# Hamamatsu_acond.net
KiCad netlist of a schematic drawn in Altium Designer
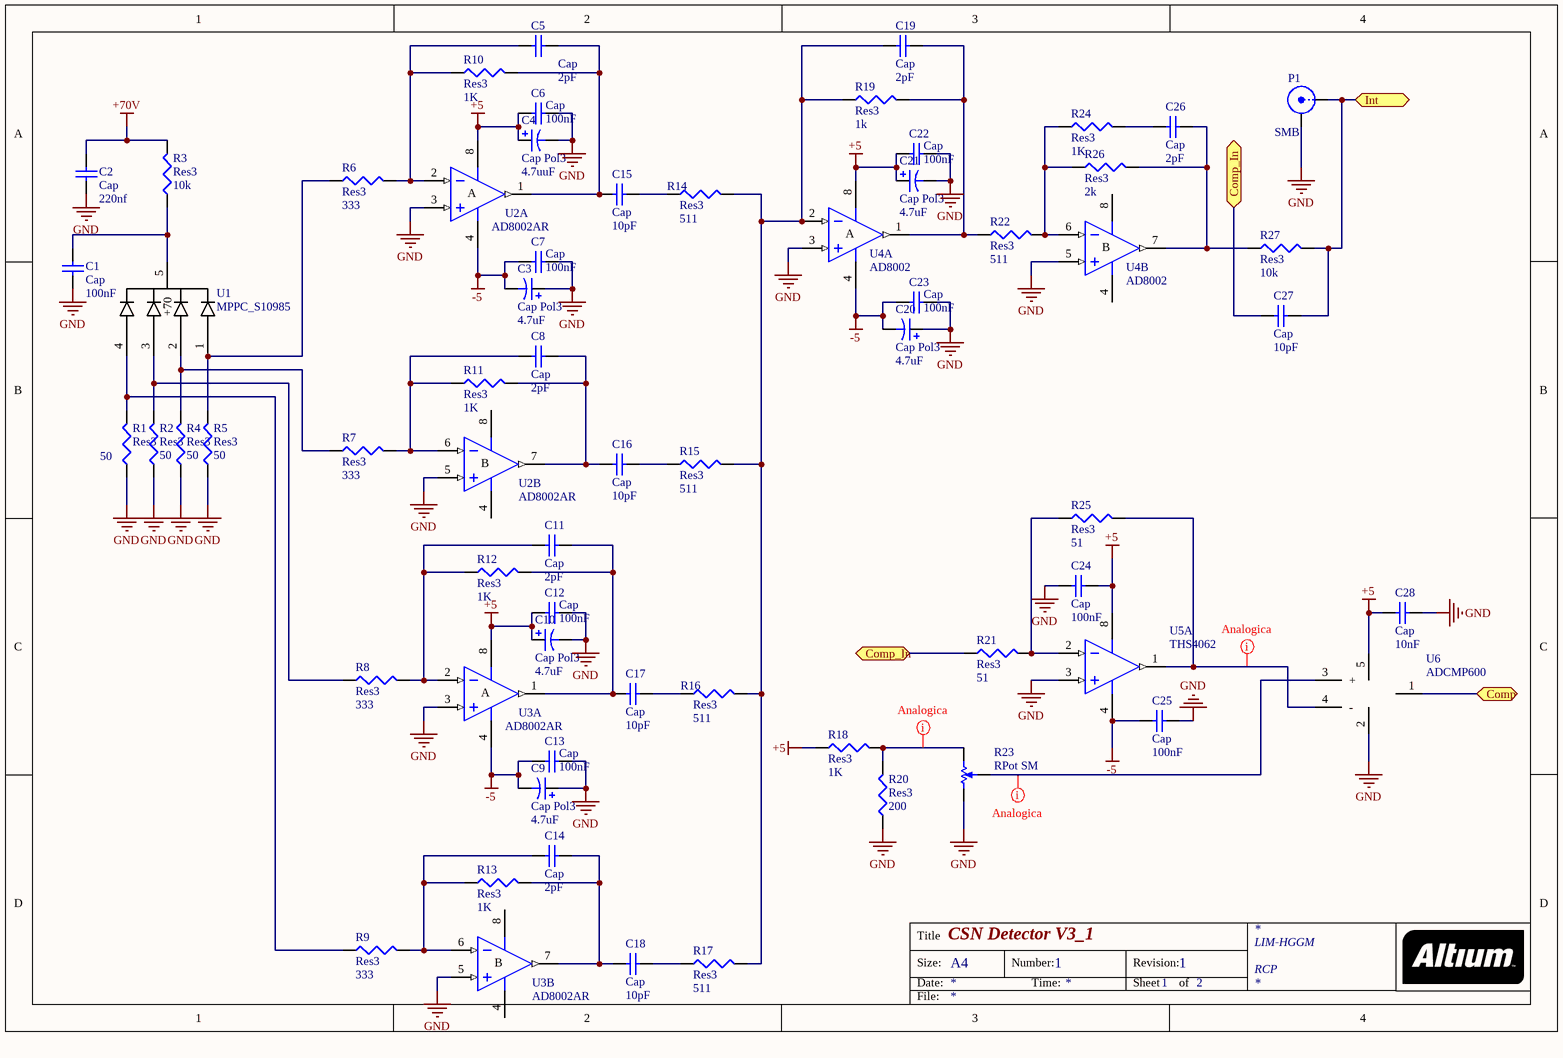
[diagram p0: Hamamatsu_acond.SchDoc]

(export (version "E")
  (design (tool "Eeschema 10.0.6"))
  (components
    (comp (ref "C1")
      (value "Cap")
      (footprint "C0805")
      (description "Capacitor")
      (fields (field (name "ALTIUM_VALUE") "100nF") (field (name "PUBLISHER") "Altium Limited"))
      (libsource (lib "Miscellaneous Devices") (part "Cap"))
    )
    (comp (ref "C2")
      (value "Cap")
      (footprint "C0805")
      (description "Capacitor")
      (fields (field (name "ALTIUM_VALUE") "220nf") (field (name "PUBLISHER") "Altium Limited"))
      (libsource (lib "Miscellaneous Devices") (part "Cap"))
    )
    (comp (ref "C3")
      (value "Cap Pol3")
      (footprint "6-0805_N")
      (description "Polarized Capacitor (Surface Mount)")
      (fields (field (name "ALTIUM_VALUE") "4.7uF") (field (name "PUBLISHER") "Altium Limited"))
      (libsource (lib "Miscellaneous Devices") (part "Cap Pol3"))
    )
    (comp (ref "C4")
      (value "Cap Pol3")
      (footprint "6-0805_N")
      (description "Polarized Capacitor (Surface Mount)")
      (fields (field (name "ALTIUM_VALUE") "4.7uuF") (field (name "PUBLISHER") "Altium Limited"))
      (libsource (lib "Miscellaneous Devices") (part "Cap Pol3"))
    )
    (comp (ref "C5")
      (value "Cap")
      (footprint "C0805")
      (description "Capacitor")
      (fields (field (name "ALTIUM_VALUE") "2pF") (field (name "PUBLISHER") "Altium Limited"))
      (libsource (lib "Miscellaneous Devices") (part "Cap"))
    )
    (comp (ref "C6")
      (value "Cap")
      (footprint "6-0805_N")
      (description "Capacitor")
      (fields (field (name "ALTIUM_VALUE") "100nF") (field (name "PUBLISHER") "Altium Limited"))
      (libsource (lib "Miscellaneous Devices") (part "Cap"))
    )
    (comp (ref "C7")
      (value "Cap")
      (footprint "6-0805_N")
      (description "Capacitor")
      (fields (field (name "ALTIUM_VALUE") "100nF") (field (name "PUBLISHER") "Altium Limited"))
      (libsource (lib "Miscellaneous Devices") (part "Cap"))
    )
    (comp (ref "C8")
      (value "Cap")
      (footprint "C0805")
      (description "Capacitor")
      (fields (field (name "ALTIUM_VALUE") "2pF") (field (name "PUBLISHER") "Altium Limited"))
      (libsource (lib "Miscellaneous Devices") (part "Cap"))
    )
    (comp (ref "C9")
      (value "Cap Pol3")
      (footprint "6-0805_N")
      (description "Polarized Capacitor (Surface Mount)")
      (fields (field (name "ALTIUM_VALUE") "4.7uF") (field (name "PUBLISHER") "Altium Limited"))
      (libsource (lib "Miscellaneous Devices") (part "Cap Pol3"))
    )
    (comp (ref "C10")
      (value "Cap Pol3")
      (footprint "6-0805_N")
      (description "Polarized Capacitor (Surface Mount)")
      (fields (field (name "ALTIUM_VALUE") "4.7uF") (field (name "PUBLISHER") "Altium Limited"))
      (libsource (lib "Miscellaneous Devices") (part "Cap Pol3"))
    )
    (comp (ref "C11")
      (value "Cap")
      (footprint "C0805")
      (description "Capacitor")
      (fields (field (name "ALTIUM_VALUE") "2pF") (field (name "PUBLISHER") "Altium Limited"))
      (libsource (lib "Miscellaneous Devices") (part "Cap"))
    )
    (comp (ref "C12")
      (value "Cap")
      (footprint "6-0805_N")
      (description "Capacitor")
      (fields (field (name "ALTIUM_VALUE") "100nF") (field (name "PUBLISHER") "Altium Limited"))
      (libsource (lib "Miscellaneous Devices") (part "Cap"))
    )
    (comp (ref "C13")
      (value "Cap")
      (footprint "6-0805_N")
      (description "Capacitor")
      (fields (field (name "ALTIUM_VALUE") "100nF") (field (name "PUBLISHER") "Altium Limited"))
      (libsource (lib "Miscellaneous Devices") (part "Cap"))
    )
    (comp (ref "C14")
      (value "Cap")
      (footprint "C0805")
      (description "Capacitor")
      (fields (field (name "ALTIUM_VALUE") "2pF") (field (name "PUBLISHER") "Altium Limited"))
      (libsource (lib "Miscellaneous Devices") (part "Cap"))
    )
    (comp (ref "C15")
      (value "Cap")
      (footprint "C0805")
      (description "Capacitor")
      (fields (field (name "ALTIUM_VALUE") "10pF") (field (name "PUBLISHER") "Altium Limited"))
      (libsource (lib "Miscellaneous Devices") (part "Cap"))
    )
    (comp (ref "C16")
      (value "Cap")
      (footprint "C0805")
      (description "Capacitor")
      (fields (field (name "ALTIUM_VALUE") "10pF") (field (name "PUBLISHER") "Altium Limited"))
      (libsource (lib "Miscellaneous Devices") (part "Cap"))
    )
    (comp (ref "C17")
      (value "Cap")
      (footprint "C0805")
      (description "Capacitor")
      (fields (field (name "ALTIUM_VALUE") "10pF") (field (name "PUBLISHER") "Altium Limited"))
      (libsource (lib "Miscellaneous Devices") (part "Cap"))
    )
    (comp (ref "C18")
      (value "Cap")
      (footprint "C0805")
      (description "Capacitor")
      (fields (field (name "ALTIUM_VALUE") "10pF") (field (name "PUBLISHER") "Altium Limited"))
      (libsource (lib "Miscellaneous Devices") (part "Cap"))
    )
    (comp (ref "C19")
      (value "Cap")
      (footprint "C0805")
      (description "Capacitor")
      (fields (field (name "ALTIUM_VALUE") "2pF") (field (name "PUBLISHER") "Altium Limited"))
      (libsource (lib "Miscellaneous Devices") (part "Cap"))
    )
    (comp (ref "C20")
      (value "Cap Pol3")
      (footprint "6-0805_N")
      (description "Polarized Capacitor (Surface Mount)")
      (fields (field (name "ALTIUM_VALUE") "4.7uF") (field (name "PUBLISHER") "Altium Limited"))
      (libsource (lib "Miscellaneous Devices") (part "Cap Pol3"))
    )
    (comp (ref "C21")
      (value "Cap Pol3")
      (footprint "6-0805_N")
      (description "Polarized Capacitor (Surface Mount)")
      (fields (field (name "ALTIUM_VALUE") "4.7uF") (field (name "PUBLISHER") "Altium Limited"))
      (libsource (lib "Miscellaneous Devices") (part "Cap Pol3"))
    )
    (comp (ref "C22")
      (value "Cap")
      (footprint "6-0805_N")
      (description "Capacitor")
      (fields (field (name "ALTIUM_VALUE") "100nF") (field (name "PUBLISHER") "Altium Limited"))
      (libsource (lib "Miscellaneous Devices") (part "Cap"))
    )
    (comp (ref "C23")
      (value "Cap")
      (footprint "6-0805_N")
      (description "Capacitor")
      (fields (field (name "ALTIUM_VALUE") "100nF") (field (name "PUBLISHER") "Altium Limited"))
      (libsource (lib "Miscellaneous Devices") (part "Cap"))
    )
    (comp (ref "C24")
      (value "Cap")
      (footprint "6-0805_N")
      (description "Capacitor")
      (fields (field (name "ALTIUM_VALUE") "100nF") (field (name "PUBLISHER") "Altium Limited"))
      (libsource (lib "Miscellaneous Devices") (part "Cap"))
    )
    (comp (ref "C25")
      (value "Cap")
      (footprint "6-0805_N")
      (description "Capacitor")
      (fields (field (name "ALTIUM_VALUE") "100nF") (field (name "PUBLISHER") "Altium Limited"))
      (libsource (lib "Miscellaneous Devices") (part "Cap"))
    )
    (comp (ref "C26")
      (value "Cap")
      (footprint "C0805")
      (description "Capacitor")
      (fields (field (name "ALTIUM_VALUE") "2pF") (field (name "PUBLISHER") "Altium Limited"))
      (libsource (lib "Miscellaneous Devices") (part "Cap"))
    )
    (comp (ref "C27")
      (value "Cap")
      (footprint "C0805")
      (description "Capacitor")
      (fields (field (name "ALTIUM_VALUE") "10pF") (field (name "PUBLISHER") "Altium Limited"))
      (libsource (lib "Miscellaneous Devices") (part "Cap"))
    )
    (comp (ref "C28")
      (value "Cap")
      (footprint "6-0805_N")
      (description "Capacitor")
      (fields (field (name "ALTIUM_VALUE") "10nF") (field (name "PUBLISHER") "Altium Limited"))
      (libsource (lib "Miscellaneous Devices") (part "Cap"))
    )
    (comp (ref "P1")
      (value "SMB")
      (footprint "SMB_V-RJ45")
      (description "SMB Straight Connector")
      (fields (field (name "PUBLISHER") "Altium Limited"))
      (libsource (lib "Miscellaneous Connectors") (part "SMB"))
    )
    (comp (ref "R1")
      (value "Res3")
      (footprint "6-0805_N")
      (description "Resistor")
      (fields (field (name "ALTIUM_VALUE") "50") (field (name "PUBLISHER") "Altium Limited"))
      (libsource (lib "Miscellaneous Devices") (part "Res3"))
    )
    (comp (ref "R2")
      (value "Res3")
      (footprint "6-0805_N")
      (description "Resistor")
      (fields (field (name "ALTIUM_VALUE") "50") (field (name "PUBLISHER") "Altium Limited"))
      (libsource (lib "Miscellaneous Devices") (part "Res3"))
    )
    (comp (ref "R3")
      (value "Res3")
      (footprint "6-0805_N")
      (description "Resistor")
      (fields (field (name "ALTIUM_VALUE") "10k") (field (name "PUBLISHER") "Altium Limited"))
      (libsource (lib "Miscellaneous Devices") (part "Res3"))
    )
    (comp (ref "R4")
      (value "Res3")
      (footprint "6-0805_N")
      (description "Resistor")
      (fields (field (name "ALTIUM_VALUE") "50") (field (name "PUBLISHER") "Altium Limited"))
      (libsource (lib "Miscellaneous Devices") (part "Res3"))
    )
    (comp (ref "R5")
      (value "Res3")
      (footprint "6-0805_N")
      (description "Resistor")
      (fields (field (name "ALTIUM_VALUE") "50") (field (name "PUBLISHER") "Altium Limited"))
      (libsource (lib "Miscellaneous Devices") (part "Res3"))
    )
    (comp (ref "R6")
      (value "Res3")
      (footprint "6-0805_N")
      (description "Resistor")
      (fields (field (name "ALTIUM_VALUE") "333") (field (name "PUBLISHER") "Altium Limited"))
      (libsource (lib "Miscellaneous Devices") (part "Res3"))
    )
    (comp (ref "R7")
      (value "Res3")
      (footprint "6-0805_N")
      (description "Resistor")
      (fields (field (name "ALTIUM_VALUE") "333") (field (name "PUBLISHER") "Altium Limited"))
      (libsource (lib "Miscellaneous Devices") (part "Res3"))
    )
    (comp (ref "R8")
      (value "Res3")
      (footprint "6-0805_N")
      (description "Resistor")
      (fields (field (name "ALTIUM_VALUE") "333") (field (name "PUBLISHER") "Altium Limited"))
      (libsource (lib "Miscellaneous Devices") (part "Res3"))
    )
    (comp (ref "R9")
      (value "Res3")
      (footprint "6-0805_N")
      (description "Resistor")
      (fields (field (name "ALTIUM_VALUE") "333") (field (name "PUBLISHER") "Altium Limited"))
      (libsource (lib "Miscellaneous Devices") (part "Res3"))
    )
    (comp (ref "R10")
      (value "Res3")
      (footprint "6-0805_N")
      (description "Resistor")
      (fields (field (name "ALTIUM_VALUE") "1K") (field (name "PUBLISHER") "Altium Limited"))
      (libsource (lib "Miscellaneous Devices") (part "Res3"))
    )
    (comp (ref "R11")
      (value "Res3")
      (footprint "6-0805_N")
      (description "Resistor")
      (fields (field (name "ALTIUM_VALUE") "1K") (field (name "PUBLISHER") "Altium Limited"))
      (libsource (lib "Miscellaneous Devices") (part "Res3"))
    )
    (comp (ref "R12")
      (value "Res3")
      (footprint "6-0805_N")
      (description "Resistor")
      (fields (field (name "ALTIUM_VALUE") "1K") (field (name "PUBLISHER") "Altium Limited"))
      (libsource (lib "Miscellaneous Devices") (part "Res3"))
    )
    (comp (ref "R13")
      (value "Res3")
      (footprint "6-0805_N")
      (description "Resistor")
      (fields (field (name "ALTIUM_VALUE") "1K") (field (name "PUBLISHER") "Altium Limited"))
      (libsource (lib "Miscellaneous Devices") (part "Res3"))
    )
    (comp (ref "R14")
      (value "Res3")
      (footprint "6-0805_N")
      (description "Resistor")
      (fields (field (name "ALTIUM_VALUE") "511") (field (name "PUBLISHER") "Altium Limited"))
      (libsource (lib "Miscellaneous Devices") (part "Res3"))
    )
    (comp (ref "R15")
      (value "Res3")
      (footprint "6-0805_N")
      (description "Resistor")
      (fields (field (name "ALTIUM_VALUE") "511") (field (name "PUBLISHER") "Altium Limited"))
      (libsource (lib "Miscellaneous Devices") (part "Res3"))
    )
    (comp (ref "R16")
      (value "Res3")
      (footprint "6-0805_N")
      (description "Resistor")
      (fields (field (name "ALTIUM_VALUE") "511") (field (name "PUBLISHER") "Altium Limited"))
      (libsource (lib "Miscellaneous Devices") (part "Res3"))
    )
    (comp (ref "R17")
      (value "Res3")
      (footprint "6-0805_N")
      (description "Resistor")
      (fields (field (name "ALTIUM_VALUE") "511") (field (name "PUBLISHER") "Altium Limited"))
      (libsource (lib "Miscellaneous Devices") (part "Res3"))
    )
    (comp (ref "R18")
      (value "Res3")
      (footprint "6-0805_N")
      (description "Resistor")
      (fields (field (name "ALTIUM_VALUE") "1K") (field (name "PUBLISHER") "Altium Limited"))
      (libsource (lib "Miscellaneous Devices") (part "Res3"))
    )
    (comp (ref "R19")
      (value "Res3")
      (footprint "6-0805_N")
      (description "Resistor")
      (fields (field (name "ALTIUM_VALUE") "1k") (field (name "PUBLISHER") "Altium Limited"))
      (libsource (lib "Miscellaneous Devices") (part "Res3"))
    )
    (comp (ref "R20")
      (value "Res3")
      (footprint "6-0805_N")
      (description "Resistor")
      (fields (field (name "ALTIUM_VALUE") "200") (field (name "PUBLISHER") "Altium Limited"))
      (libsource (lib "Miscellaneous Devices") (part "Res3"))
    )
    (comp (ref "R21")
      (value "Res3")
      (footprint "6-0805_N")
      (description "Resistor")
      (fields (field (name "ALTIUM_VALUE") "51") (field (name "PUBLISHER") "Altium Limited"))
      (libsource (lib "Miscellaneous Devices") (part "Res3"))
    )
    (comp (ref "R22")
      (value "Res3")
      (footprint "6-0805_N")
      (description "Resistor")
      (fields (field (name "ALTIUM_VALUE") "511") (field (name "PUBLISHER") "Altium Limited"))
      (libsource (lib "Miscellaneous Devices") (part "Res3"))
    )
    (comp (ref "R23")
      (value "RPot SM")
      (footprint "POT4MM-2")
      (description "Square Trimming Potentiometer")
      (fields (field (name "PUBLISHER") "Altium Limited"))
      (libsource (lib "Miscellaneous Devices") (part "RPot SM"))
    )
    (comp (ref "R24")
      (value "Res3")
      (footprint "6-0805_N")
      (description "Resistor")
      (fields (field (name "ALTIUM_VALUE") "1K") (field (name "PUBLISHER") "Altium Limited"))
      (libsource (lib "Miscellaneous Devices") (part "Res3"))
    )
    (comp (ref "R25")
      (value "Res3")
      (footprint "6-0805_N")
      (description "Resistor")
      (fields (field (name "ALTIUM_VALUE") "51") (field (name "PUBLISHER") "Altium Limited"))
      (libsource (lib "Miscellaneous Devices") (part "Res3"))
    )
    (comp (ref "R26")
      (value "Res3")
      (footprint "6-0805_N")
      (description "Resistor")
      (fields (field (name "ALTIUM_VALUE") "2k") (field (name "PUBLISHER") "Altium Limited"))
      (libsource (lib "Miscellaneous Devices") (part "Res3"))
    )
    (comp (ref "R27")
      (value "Res3")
      (footprint "6-0805_N")
      (description "Resistor")
      (fields (field (name "ALTIUM_VALUE") "10k") (field (name "PUBLISHER") "Altium Limited"))
      (libsource (lib "Miscellaneous Devices") (part "Res3"))
    )
    (comp (ref "U1")
      (value "MPPC_S10985")
      (footprint "S10985_HAM")
      (libsource (lib "Schlib1") (part "MPPC_S10985"))
    )
    (comp (ref "U2")
      (value "AD8002AR")
      (footprint "SO-8_M")
      (description "Dual 600MHz, 50mW Current Feedback Amplifier")
      (fields (field (name "PUBLISHER") "Altium Limited"))
      (libsource (lib "AD Operational Amplifier") (part "AD8002AR"))
    )
    (comp (ref "U3")
      (value "AD8002AR")
      (footprint "SO-8_M")
      (description "Dual 600MHz, 50mW Current Feedback Amplifier")
      (fields (field (name "PUBLISHER") "Altium Limited"))
      (libsource (lib "AD Operational Amplifier") (part "AD8002AR"))
    )
    (comp (ref "U4")
      (value "AD8002")
      (footprint "SO-8_M")
      (description "Dual 600MHz, 50mW Current Feedback Amplifier")
      (fields (field (name "PUBLISHER") "Altium Limited"))
      (libsource (lib "AD Operational Amplifier") (part "AD8002AR"))
    )
    (comp (ref "U5")
      (value "THS4062")
      (footprint "S8_N")
      (description "Low Cost Dual Video Amplifier")
      (fields (field (name "PUBLISHER") "Altium Limited"))
      (libsource (lib "LT Video Amplifier") (part "LT1253CS8"))
    )
    (comp (ref "U6") (value "ADCMP600") (footprint "SOT23-5_N") (libsource (lib "Schlib1") (part "ADCMP600")))
  )
  (nets
    (net (code "1") (name "+5") (class "Default")
      (node (ref "C10") (pin "1") (pinfunction "1_1") (pintype "passive"))
      (node (ref "C12") (pin "2") (pinfunction "2_2") (pintype "passive"))
      (node (ref "C21") (pin "1") (pinfunction "1_1") (pintype "passive"))
      (node (ref "C22") (pin "2") (pinfunction "2_2") (pintype "passive"))
      (node (ref "C24") (pin "2") (pinfunction "2_2") (pintype "passive"))
      (node (ref "C28") (pin "1") (pinfunction "1_1") (pintype "passive"))
      (node (ref "C4") (pin "1") (pinfunction "1_1") (pintype "passive"))
      (node (ref "C6") (pin "2") (pinfunction "2_2") (pintype "passive"))
      (node (ref "R18") (pin "1") (pinfunction "1_1") (pintype "passive"))
      (node (ref "U2") (pin "8") (pinfunction "V+_8") (pintype "power_in"))
      (node (ref "U3") (pin "8") (pinfunction "V+_8") (pintype "power_in"))
      (node (ref "U4") (pin "8") (pinfunction "V+_8") (pintype "power_in"))
      (node (ref "U5") (pin "8") (pinfunction "V+_8") (pintype "power_in"))
      (node (ref "U6") (pin "5") (pintype "power_in"))
    )
    (net (code "2") (name "+70V") (class "Default")
      (node (ref "C2") (pin "2") (pinfunction "2_2") (pintype "passive"))
      (node (ref "R3") (pin "2") (pinfunction "2_2") (pintype "passive"))
    )
    (net (code "3") (name "-5") (class "Default")
      (node (ref "C13") (pin "2") (pinfunction "2_2") (pintype "passive"))
      (node (ref "C20") (pin "2") (pinfunction "2_2") (pintype "passive"))
      (node (ref "C23") (pin "2") (pinfunction "2_2") (pintype "passive"))
      (node (ref "C25") (pin "1") (pinfunction "1_1") (pintype "passive"))
      (node (ref "C3") (pin "2") (pinfunction "2_2") (pintype "passive"))
      (node (ref "C7") (pin "2") (pinfunction "2_2") (pintype "passive"))
      (node (ref "C9") (pin "2") (pinfunction "2_2") (pintype "passive"))
      (node (ref "U2") (pin "4") (pinfunction "V-_4") (pintype "power_in"))
      (node (ref "U3") (pin "4") (pinfunction "V-_4") (pintype "power_in"))
      (node (ref "U4") (pin "4") (pinfunction "V-_4") (pintype "power_in"))
      (node (ref "U5") (pin "4") (pinfunction "V-_4") (pintype "power_in"))
    )
    (net (code "4") (name "/Comp") (class "Default") (node (ref "U6") (pin "1") (pintype "passive")))
    (net (code "5") (name "/Comp_In") (class "Default")
      (node (ref "C27") (pin "1") (pinfunction "1_1") (pintype "passive"))
      (node (ref "R21") (pin "1") (pinfunction "1_1") (pintype "passive"))
    )
    (net (code "6") (name "/Int") (class "Default")
      (node (ref "C27") (pin "2") (pinfunction "2_2") (pintype "passive"))
      (node (ref "P1") (pin "1") (pinfunction "X_1") (pintype "passive"))
      (node (ref "R27") (pin "2") (pinfunction "2_2") (pintype "passive"))
    )
    (net (code "7") (name "GND") (class "Default")
      (node (ref "C1") (pin "1") (pinfunction "1_1") (pintype "passive"))
      (node (ref "C10") (pin "2") (pinfunction "2_2") (pintype "passive"))
      (node (ref "C12") (pin "1") (pinfunction "1_1") (pintype "passive"))
      (node (ref "C13") (pin "1") (pinfunction "1_1") (pintype "passive"))
      (node (ref "C2") (pin "1") (pinfunction "1_1") (pintype "passive"))
      (node (ref "C20") (pin "1") (pinfunction "1_1") (pintype "passive"))
      (node (ref "C21") (pin "2") (pinfunction "2_2") (pintype "passive"))
      (node (ref "C22") (pin "1") (pinfunction "1_1") (pintype "passive"))
      (node (ref "C23") (pin "1") (pinfunction "1_1") (pintype "passive"))
      (node (ref "C24") (pin "1") (pinfunction "1_1") (pintype "passive"))
      (node (ref "C25") (pin "2") (pinfunction "2_2") (pintype "passive"))
      (node (ref "C28") (pin "2") (pinfunction "2_2") (pintype "passive"))
      (node (ref "C3") (pin "1") (pinfunction "1_1") (pintype "passive"))
      (node (ref "C4") (pin "2") (pinfunction "2_2") (pintype "passive"))
      (node (ref "C6") (pin "1") (pinfunction "1_1") (pintype "passive"))
      (node (ref "C7") (pin "1") (pinfunction "1_1") (pintype "passive"))
      (node (ref "C9") (pin "1") (pinfunction "1_1") (pintype "passive"))
      (node (ref "P1") (pin "2") (pinfunction "Y_2") (pintype "passive"))
      (node (ref "R1") (pin "1") (pinfunction "1_1") (pintype "passive"))
      (node (ref "R2") (pin "1") (pinfunction "1_1") (pintype "passive"))
      (node (ref "R20") (pin "1") (pinfunction "1_1") (pintype "passive"))
      (node (ref "R23") (pin "CCW") (pinfunction "-_CCW") (pintype "passive"))
      (node (ref "R4") (pin "1") (pinfunction "1_1") (pintype "passive"))
      (node (ref "R5") (pin "1") (pinfunction "1_1") (pintype "passive"))
      (node (ref "U2") (pin "3") (pinfunction "IN+_3") (pintype "input"))
      (node (ref "U2") (pin "5") (pinfunction "IN+_5") (pintype "input"))
      (node (ref "U3") (pin "3") (pinfunction "IN+_3") (pintype "input"))
      (node (ref "U3") (pin "5") (pinfunction "IN+_5") (pintype "input"))
      (node (ref "U4") (pin "3") (pinfunction "IN+_3") (pintype "input"))
      (node (ref "U4") (pin "5") (pinfunction "IN+_5") (pintype "input"))
      (node (ref "U5") (pin "3") (pinfunction "IN+_3") (pintype "input"))
      (node (ref "U6") (pin "2") (pintype "power_in"))
    )
    (net (code "8") (name "Net-(C15-Pad2)") (class "Default")
      (node (ref "C15") (pin "2") (pinfunction "2_2") (pintype "passive"))
      (node (ref "R14") (pin "1") (pinfunction "1_1") (pintype "passive"))
    )
    (net (code "9") (name "Net-(C16-Pad2)") (class "Default")
      (node (ref "C16") (pin "2") (pinfunction "2_2") (pintype "passive"))
      (node (ref "R15") (pin "1") (pinfunction "1_1") (pintype "passive"))
    )
    (net (code "10") (name "Net-(C17-Pad2)") (class "Default")
      (node (ref "C17") (pin "2") (pinfunction "2_2") (pintype "passive"))
      (node (ref "R16") (pin "1") (pinfunction "1_1") (pintype "passive"))
    )
    (net (code "11") (name "Net-(C18-Pad2)") (class "Default")
      (node (ref "C18") (pin "2") (pinfunction "2_2") (pintype "passive"))
      (node (ref "R17") (pin "1") (pinfunction "1_1") (pintype "passive"))
    )
    (net (code "12") (name "Net-(C26-Pad1)") (class "Default")
      (node (ref "C26") (pin "1") (pinfunction "1_1") (pintype "passive"))
      (node (ref "R24") (pin "2") (pinfunction "2_2") (pintype "passive"))
    )
    (net (code "13") (name "Net-(R1-Pad2)") (class "Default")
      (node (ref "R1") (pin "2") (pinfunction "2_2") (pintype "passive"))
      (node (ref "R9") (pin "1") (pinfunction "1_1") (pintype "passive"))
      (node (ref "U1") (pin "4") (pinfunction "4_4") (pintype "passive"))
    )
    (net (code "14") (name "Net-(R2-Pad2)") (class "Default")
      (node (ref "R2") (pin "2") (pinfunction "2_2") (pintype "passive"))
      (node (ref "R8") (pin "1") (pinfunction "1_1") (pintype "passive"))
      (node (ref "U1") (pin "3") (pinfunction "3_3") (pintype "passive"))
    )
    (net (code "15") (name "Net-(R23-+)") (class "Default")
      (node (ref "R18") (pin "2") (pinfunction "2_2") (pintype "passive"))
      (node (ref "R20") (pin "2") (pinfunction "2_2") (pintype "passive"))
      (node (ref "R23") (pin "CW") (pinfunction "+_CW") (pintype "passive"))
    )
    (net (code "16") (name "Net-(U1-+70)") (class "Default")
      (node (ref "C1") (pin "2") (pinfunction "2_2") (pintype "passive"))
      (node (ref "R3") (pin "1") (pinfunction "1_1") (pintype "passive"))
      (node (ref "U1") (pin "5") (pinfunction "+70_5") (pintype "passive"))
    )
    (net (code "17") (name "Net-(U1-Pin1)") (class "Default")
      (node (ref "R5") (pin "2") (pinfunction "2_2") (pintype "passive"))
      (node (ref "R6") (pin "1") (pinfunction "1_1") (pintype "passive"))
      (node (ref "U1") (pin "1") (pinfunction "Pin1_1") (pintype "passive"))
    )
    (net (code "18") (name "Net-(U1-Pin2)") (class "Default")
      (node (ref "R4") (pin "2") (pinfunction "2_2") (pintype "passive"))
      (node (ref "R7") (pin "1") (pinfunction "1_1") (pintype "passive"))
      (node (ref "U1") (pin "2") (pinfunction "Pin2_2") (pintype "passive"))
    )
    (net (code "19") (name "Net-(U2A-IN-)") (class "Default")
      (node (ref "C5") (pin "1") (pinfunction "1_1") (pintype "passive"))
      (node (ref "R10") (pin "1") (pinfunction "1_1") (pintype "passive"))
      (node (ref "R6") (pin "2") (pinfunction "2_2") (pintype "passive"))
      (node (ref "U2") (pin "2") (pinfunction "IN-_2") (pintype "input"))
    )
    (net (code "20") (name "Net-(U2A-OUT)") (class "Default")
      (node (ref "C15") (pin "1") (pinfunction "1_1") (pintype "passive"))
      (node (ref "C5") (pin "2") (pinfunction "2_2") (pintype "passive"))
      (node (ref "R10") (pin "2") (pinfunction "2_2") (pintype "passive"))
      (node (ref "U2") (pin "1") (pinfunction "OUT_1") (pintype "output"))
    )
    (net (code "21") (name "Net-(U2B-IN-)") (class "Default")
      (node (ref "C8") (pin "1") (pinfunction "1_1") (pintype "passive"))
      (node (ref "R11") (pin "1") (pinfunction "1_1") (pintype "passive"))
      (node (ref "R7") (pin "2") (pinfunction "2_2") (pintype "passive"))
      (node (ref "U2") (pin "6") (pinfunction "IN-_6") (pintype "input"))
    )
    (net (code "22") (name "Net-(U2B-OUT)") (class "Default")
      (node (ref "C16") (pin "1") (pinfunction "1_1") (pintype "passive"))
      (node (ref "C8") (pin "2") (pinfunction "2_2") (pintype "passive"))
      (node (ref "R11") (pin "2") (pinfunction "2_2") (pintype "passive"))
      (node (ref "U2") (pin "7") (pinfunction "OUT_7") (pintype "output"))
    )
    (net (code "23") (name "Net-(U3A-IN-)") (class "Default")
      (node (ref "C11") (pin "1") (pinfunction "1_1") (pintype "passive"))
      (node (ref "R12") (pin "1") (pinfunction "1_1") (pintype "passive"))
      (node (ref "R8") (pin "2") (pinfunction "2_2") (pintype "passive"))
      (node (ref "U3") (pin "2") (pinfunction "IN-_2") (pintype "input"))
    )
    (net (code "24") (name "Net-(U3A-OUT)") (class "Default")
      (node (ref "C11") (pin "2") (pinfunction "2_2") (pintype "passive"))
      (node (ref "C17") (pin "1") (pinfunction "1_1") (pintype "passive"))
      (node (ref "R12") (pin "2") (pinfunction "2_2") (pintype "passive"))
      (node (ref "U3") (pin "1") (pinfunction "OUT_1") (pintype "output"))
    )
    (net (code "25") (name "Net-(U3B-IN-)") (class "Default")
      (node (ref "C14") (pin "1") (pinfunction "1_1") (pintype "passive"))
      (node (ref "R13") (pin "1") (pinfunction "1_1") (pintype "passive"))
      (node (ref "R9") (pin "2") (pinfunction "2_2") (pintype "passive"))
      (node (ref "U3") (pin "6") (pinfunction "IN-_6") (pintype "input"))
    )
    (net (code "26") (name "Net-(U3B-OUT)") (class "Default")
      (node (ref "C14") (pin "2") (pinfunction "2_2") (pintype "passive"))
      (node (ref "C18") (pin "1") (pinfunction "1_1") (pintype "passive"))
      (node (ref "R13") (pin "2") (pinfunction "2_2") (pintype "passive"))
      (node (ref "U3") (pin "7") (pinfunction "OUT_7") (pintype "output"))
    )
    (net (code "27") (name "Net-(U4A-IN-)") (class "Default")
      (node (ref "C19") (pin "1") (pinfunction "1_1") (pintype "passive"))
      (node (ref "R14") (pin "2") (pinfunction "2_2") (pintype "passive"))
      (node (ref "R15") (pin "2") (pinfunction "2_2") (pintype "passive"))
      (node (ref "R16") (pin "2") (pinfunction "2_2") (pintype "passive"))
      (node (ref "R17") (pin "2") (pinfunction "2_2") (pintype "passive"))
      (node (ref "R19") (pin "1") (pinfunction "1_1") (pintype "passive"))
      (node (ref "U4") (pin "2") (pinfunction "IN-_2") (pintype "input"))
    )
    (net (code "28") (name "Net-(U4A-OUT)") (class "Default")
      (node (ref "C19") (pin "2") (pinfunction "2_2") (pintype "passive"))
      (node (ref "R19") (pin "2") (pinfunction "2_2") (pintype "passive"))
      (node (ref "R22") (pin "1") (pinfunction "1_1") (pintype "passive"))
      (node (ref "U4") (pin "1") (pinfunction "OUT_1") (pintype "output"))
    )
    (net (code "29") (name "Net-(U4B-IN-)") (class "Default")
      (node (ref "R22") (pin "2") (pinfunction "2_2") (pintype "passive"))
      (node (ref "R24") (pin "1") (pinfunction "1_1") (pintype "passive"))
      (node (ref "R26") (pin "1") (pinfunction "1_1") (pintype "passive"))
      (node (ref "U4") (pin "6") (pinfunction "IN-_6") (pintype "input"))
    )
    (net (code "30") (name "Net-(U4B-OUT)") (class "Default")
      (node (ref "C26") (pin "2") (pinfunction "2_2") (pintype "passive"))
      (node (ref "R26") (pin "2") (pinfunction "2_2") (pintype "passive"))
      (node (ref "R27") (pin "1") (pinfunction "1_1") (pintype "passive"))
      (node (ref "U4") (pin "7") (pinfunction "OUT_7") (pintype "output"))
    )
    (net (code "31") (name "Net-(U5A-IN-)") (class "Default")
      (node (ref "R21") (pin "2") (pinfunction "2_2") (pintype "passive"))
      (node (ref "R25") (pin "1") (pinfunction "1_1") (pintype "passive"))
      (node (ref "U5") (pin "2") (pinfunction "IN-_2") (pintype "input"))
    )
    (net (code "32") (name "Net-(U5A-OUT)") (class "Default")
      (node (ref "R25") (pin "2") (pinfunction "2_2") (pintype "passive"))
      (node (ref "U5") (pin "1") (pinfunction "OUT_1") (pintype "output"))
      (node (ref "U6") (pin "4") (pinfunction "-_4") (pintype "passive"))
    )
    (net (code "33") (name "Net-(U6-+)") (class "Default")
      (node (ref "R23") (pin "W") (pinfunction "W_W") (pintype "passive"))
      (node (ref "U6") (pin "3") (pinfunction "+_3") (pintype "passive"))
    )
    (net (code "34") (name "unconnected-(U2B-V+-Pad8)") (class "Default")
      (node (ref "U2") (pin "8") (pinfunction "V+_8") (pintype "power_in"))
    )
    (net (code "35") (name "unconnected-(U2B-V--Pad4)") (class "Default")
      (node (ref "U2") (pin "4") (pinfunction "V-_4") (pintype "power_in"))
    )
    (net (code "36") (name "unconnected-(U3B-V+-Pad8)") (class "Default")
      (node (ref "U3") (pin "8") (pinfunction "V+_8") (pintype "power_in"))
    )
    (net (code "37") (name "unconnected-(U3B-V--Pad4)") (class "Default")
      (node (ref "U3") (pin "4") (pinfunction "V-_4") (pintype "power_in"))
    )
    (net (code "38") (name "unconnected-(U4B-V+-Pad8)") (class "Default")
      (node (ref "U4") (pin "8") (pinfunction "V+_8") (pintype "power_in"))
    )
    (net (code "39") (name "unconnected-(U4B-V--Pad4)") (class "Default")
      (node (ref "U4") (pin "4") (pinfunction "V-_4") (pintype "power_in"))
    )
  )
)
